# INA220.net
KiCad netlist of a schematic drawn in Altium Designer
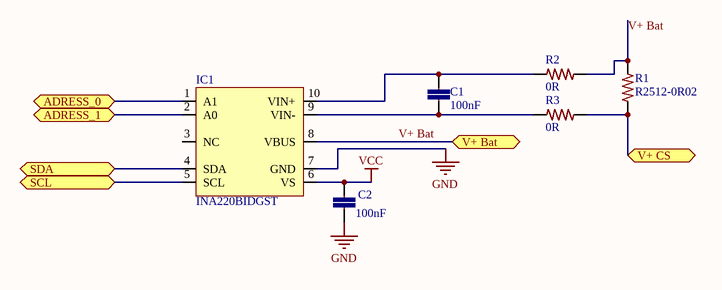
[diagram p0: INA220.SchDoc]

(export (version "E")
  (design (tool "Eeschema 10.0.6"))
  (components
    (comp (ref "C1")
      (value "100nF")
      (footprint "0402-CAP")
      (description "CAP CER 0.1UF 10V 20% X5R 0402")
      (fields (field (name "PART NO") "VJ0402V104ZXQPBC"))
      (libsource (lib "IMBEL") (part "CAPACITOR"))
    )
    (comp (ref "C2")
      (value "100nF")
      (footprint "0402-CAP")
      (description "CAP CER 0.1UF 10V 20% X5R 0402")
      (fields (field (name "PART NO") "VJ0402V104ZXQPBC"))
      (libsource (lib "IMBEL") (part "CC0402-100nF-A.12"))
    )
    (comp (ref "IC1")
      (value "INA220BIDGST")
      (footprint "TSSOP10")
      (description "IC MONITOR PWR/CURR BIDIR 10MSOP")
      (libsource (lib "IMBEL") (part "INA220BIDGST-3"))
    )
    (comp (ref "R1")
      (value "R2512-0R02")
      (footprint "2512-RES-HD")
      (description "RES .02 OHM 2W 1% 2512 SMD")
      (fields (field (name "PART NO") "WSL2512R0200FEA18"))
      (libsource (lib "IMBEL") (part "R2512-0R02-4"))
    )
    (comp (ref "R2")
      (value "0R")
      (footprint "0402-RES-HD")
      (description "RES 0.0 OHM 1/16W JUMP 0402 SMD")
      (fields (field (name "PART NO") "CRCW04020000Z0ED"))
      (libsource (lib "IMBEL") (part "RESISTOR"))
    )
    (comp (ref "R3")
      (value "0R")
      (footprint "0402-RES-HD")
      (description "RES 0.0 OHM 1/16W JUMP 0402 SMD")
      (fields (field (name "PART NO") "CRCW04020000Z0ED"))
      (libsource (lib "IMBEL") (part "RESISTOR"))
    )
  )
  (nets
    (net (code "1") (name "/ADRESS_0") (class "Default")
      (node (ref "IC1") (pin "1") (pinfunction "A1_1") (pintype "passive"))
    )
    (net (code "2") (name "/ADRESS_1") (class "Default")
      (node (ref "IC1") (pin "2") (pinfunction "A0_2") (pintype "passive"))
    )
    (net (code "3") (name "/SCL") (class "Default")
      (node (ref "IC1") (pin "5") (pinfunction "SCL_5") (pintype "passive"))
    )
    (net (code "4") (name "/SDA") (class "Default")
      (node (ref "IC1") (pin "4") (pinfunction "SDA_4") (pintype "passive"))
    )
    (net (code "5") (name "/V+ Bat") (class "Default")
      (node (ref "IC1") (pin "8") (pinfunction "VBUS_8") (pintype "passive"))
      (node (ref "R1") (pin "2") (pinfunction "2_2") (pintype "passive"))
      (node (ref "R2") (pin "2") (pinfunction "2_2") (pintype "passive"))
    )
    (net (code "6") (name "/V+ CS") (class "Default")
      (node (ref "R1") (pin "1") (pinfunction "1_1") (pintype "passive"))
      (node (ref "R3") (pin "2") (pinfunction "2_2") (pintype "passive"))
    )
    (net (code "7") (name "GND") (class "Default")
      (node (ref "C2") (pin "2") (pinfunction "2_2") (pintype "passive"))
      (node (ref "IC1") (pin "7") (pinfunction "GND_7") (pintype "passive"))
    )
    (net (code "8") (name "Net-(IC1-VIN+)") (class "Default")
      (node (ref "C1") (pin "1") (pinfunction "1_1") (pintype "passive"))
      (node (ref "IC1") (pin "10") (pinfunction "VIN+_10") (pintype "passive"))
      (node (ref "R2") (pin "1") (pinfunction "1_1") (pintype "passive"))
    )
    (net (code "9") (name "Net-(IC1-VIN-)") (class "Default")
      (node (ref "C1") (pin "2") (pinfunction "2_2") (pintype "passive"))
      (node (ref "IC1") (pin "9") (pinfunction "VIN-_9") (pintype "passive"))
      (node (ref "R3") (pin "1") (pinfunction "1_1") (pintype "passive"))
    )
    (net (code "10") (name "VCC") (class "Default")
      (node (ref "C2") (pin "1") (pinfunction "1_1") (pintype "passive"))
      (node (ref "IC1") (pin "6") (pinfunction "VS_6") (pintype "passive"))
    )
    (net (code "11") (name "unconnected-(IC1-NC-Pad3)") (class "Default")
      (node (ref "IC1") (pin "3") (pinfunction "NC_3") (pintype "passive"))
    )
  )
)
